# light-painting-brush.net
KiCad netlist of a schematic drawn in EAGLE
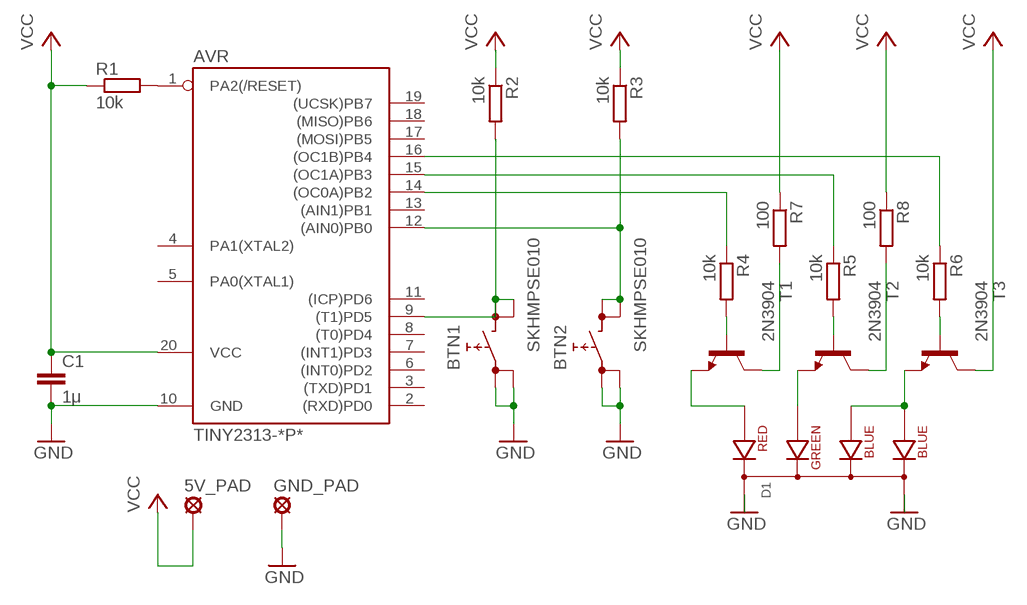
[diagram p0: schematic, sheet 1]

(export (version "E")
  (design (tool "Eeschema 10.0.6"))
  (components
    (comp (ref "5V_PAD")
      (value "LSP10")
      (footprint "eagle-import:LSP10")
      (libsource (lib "eagle-import") (part "LSP10"))
    )
    (comp (ref "AVR")
      (value "TINY2313-*P*")
      (footprint "eagle-import:DIL20")
      (libsource (lib "eagle-import") (part "TINY2313-P"))
    )
    (comp (ref "BTN1")
      (value "SKHMPSE010")
      (footprint "eagle-import:SKHMPXE010")
      (libsource (lib "eagle-import") (part "SKHMPE010S"))
    )
    (comp (ref "BTN2")
      (value "SKHMPSE010")
      (footprint "eagle-import:SKHMPXE010")
      (libsource (lib "eagle-import") (part "SKHMPE010S"))
    )
    (comp (ref "C1")
      (value "1μ")
      (footprint "eagle-import:C1206")
      (libsource (lib "eagle-import") (part "C-EUC1206"))
    )
    (comp (ref "D1")
      (value "LED-RGB-CC-THRUDIFFUSE")
      (footprint "eagle-import:LED-RGB-THRU")
      (libsource (lib "eagle-import") (part "LED-RGB-CC-THRUDIFFUSE"))
    )
    (comp (ref "GND_PAD")
      (value "LSP10")
      (footprint "eagle-import:LSP10")
      (libsource (lib "eagle-import") (part "LSP10"))
    )
    (comp (ref "R1")
      (value "10k")
      (footprint "eagle-import:R1206")
      (libsource (lib "eagle-import") (part "R-EU_R1206"))
    )
    (comp (ref "R2")
      (value "10k")
      (footprint "eagle-import:R1206")
      (libsource (lib "eagle-import") (part "R-EU_R1206"))
    )
    (comp (ref "R3")
      (value "10k")
      (footprint "eagle-import:R1206")
      (libsource (lib "eagle-import") (part "R-EU_R1206"))
    )
    (comp (ref "R4")
      (value "10k")
      (footprint "eagle-import:R1206")
      (libsource (lib "eagle-import") (part "R-EU_R1206"))
    )
    (comp (ref "R5")
      (value "10k")
      (footprint "eagle-import:R1206")
      (libsource (lib "eagle-import") (part "R-EU_R1206"))
    )
    (comp (ref "R6")
      (value "10k")
      (footprint "eagle-import:R1206")
      (libsource (lib "eagle-import") (part "R-EU_R1206"))
    )
    (comp (ref "R7")
      (value "100")
      (footprint "eagle-import:R1206")
      (libsource (lib "eagle-import") (part "R-EU_R1206"))
    )
    (comp (ref "R8")
      (value "100")
      (footprint "eagle-import:R1206")
      (libsource (lib "eagle-import") (part "R-EU_R1206"))
    )
    (comp (ref "T1")
      (value "2N3904")
      (footprint "eagle-import:TO92")
      (libsource (lib "eagle-import") (part "2N3904"))
    )
    (comp (ref "T2")
      (value "2N3904")
      (footprint "eagle-import:TO92")
      (libsource (lib "eagle-import") (part "2N3904"))
    )
    (comp (ref "T3")
      (value "2N3904")
      (footprint "eagle-import:TO92")
      (libsource (lib "eagle-import") (part "2N3904"))
    )
  )
  (nets
    (net (code "1") (name "GND") (class "Default")
      (node (ref "AVR") (pin "10") (pinfunction "GND_10") (pintype "power_in"))
      (node (ref "BTN1") (pin "1") (pinfunction "1.1_1") (pintype "passive"))
      (node (ref "BTN1") (pin "2") (pinfunction "1.2_2") (pintype "passive"))
      (node (ref "BTN2") (pin "1") (pinfunction "1.1_1") (pintype "passive"))
      (node (ref "BTN2") (pin "2") (pinfunction "1.2_2") (pintype "passive"))
      (node (ref "C1") (pin "2") (pinfunction "2_2") (pintype "passive"))
      (node (ref "D1") (pin "CATHODE1") (pinfunction "CATHODE1_CATHODE1") (pintype "bidirectional"))
      (node (ref "D1") (pin "CATHODE2") (pinfunction "CATHODE2_CATHODE2") (pintype "bidirectional"))
      (node (ref "GND_PAD") (pin "MP") (pinfunction "MP_MP") (pintype "passive"))
    )
    (net (code "2") (name "Net-(AVR-(AIN0)PB0)") (class "Default")
      (node (ref "AVR") (pin "12") (pinfunction "(AIN0)PB0_12") (pintype "bidirectional"))
      (node (ref "BTN2") (pin "3") (pinfunction "2.1_3") (pintype "passive"))
      (node (ref "BTN2") (pin "4") (pinfunction "2.2_4") (pintype "passive"))
      (node (ref "R3") (pin "2") (pinfunction "2_2") (pintype "passive"))
    )
    (net (code "3") (name "Net-(AVR-(OC0A)PB2)") (class "Default")
      (node (ref "AVR") (pin "14") (pinfunction "(OC0A)PB2_14") (pintype "bidirectional"))
      (node (ref "R4") (pin "1") (pinfunction "1_1") (pintype "passive"))
    )
    (net (code "4") (name "Net-(AVR-(OC1A)PB3)") (class "Default")
      (node (ref "AVR") (pin "15") (pinfunction "(OC1A)PB3_15") (pintype "bidirectional"))
      (node (ref "R5") (pin "1") (pinfunction "1_1") (pintype "passive"))
    )
    (net (code "5") (name "Net-(AVR-(OC1B)PB4)") (class "Default")
      (node (ref "AVR") (pin "16") (pinfunction "(OC1B)PB4_16") (pintype "bidirectional"))
      (node (ref "R6") (pin "1") (pinfunction "1_1") (pintype "passive"))
    )
    (net (code "6") (name "Net-(AVR-(T1)PD5)") (class "Default")
      (node (ref "AVR") (pin "9") (pinfunction "(T1)PD5_9") (pintype "bidirectional"))
      (node (ref "BTN1") (pin "3") (pinfunction "2.1_3") (pintype "passive"))
      (node (ref "BTN1") (pin "4") (pinfunction "2.2_4") (pintype "passive"))
      (node (ref "R2") (pin "2") (pinfunction "2_2") (pintype "passive"))
    )
    (net (code "7") (name "Net-(AVR-PA2({slash}RESET))") (class "Default")
      (node (ref "AVR") (pin "1") (pinfunction "PA2(/RESET)_1") (pintype "input"))
      (node (ref "R1") (pin "2") (pinfunction "2_2") (pintype "passive"))
    )
    (net (code "8") (name "Net-(T1-B)") (class "Default")
      (node (ref "R4") (pin "2") (pinfunction "2_2") (pintype "passive"))
      (node (ref "T1") (pin "2") (pinfunction "B_2") (pintype "passive"))
    )
    (net (code "9") (name "Net-(T1-C)") (class "Default")
      (node (ref "R7") (pin "2") (pinfunction "2_2") (pintype "passive"))
      (node (ref "T1") (pin "1") (pinfunction "C_1") (pintype "passive"))
    )
    (net (code "10") (name "Net-(T1-E)") (class "Default")
      (node (ref "D1") (pin "RED") (pinfunction "RED_RED") (pintype "bidirectional"))
      (node (ref "T1") (pin "3") (pinfunction "E_3") (pintype "passive"))
    )
    (net (code "11") (name "Net-(T2-B)") (class "Default")
      (node (ref "R5") (pin "2") (pinfunction "2_2") (pintype "passive"))
      (node (ref "T2") (pin "2") (pinfunction "B_2") (pintype "passive"))
    )
    (net (code "12") (name "Net-(T2-C)") (class "Default")
      (node (ref "R8") (pin "2") (pinfunction "2_2") (pintype "passive"))
      (node (ref "T2") (pin "1") (pinfunction "C_1") (pintype "passive"))
    )
    (net (code "13") (name "Net-(T2-E)") (class "Default")
      (node (ref "D1") (pin "GREEN") (pinfunction "GREEN_GREEN") (pintype "bidirectional"))
      (node (ref "T2") (pin "3") (pinfunction "E_3") (pintype "passive"))
    )
    (net (code "14") (name "Net-(T3-B)") (class "Default")
      (node (ref "R6") (pin "2") (pinfunction "2_2") (pintype "passive"))
      (node (ref "T3") (pin "2") (pinfunction "B_2") (pintype "passive"))
    )
    (net (code "15") (name "Net-(T3-E)") (class "Default")
      (node (ref "D1") (pin "BLUE1") (pinfunction "BLUE1_BLUE1") (pintype "bidirectional"))
      (node (ref "D1") (pin "BLUE2") (pinfunction "BLUE2_BLUE2") (pintype "bidirectional"))
      (node (ref "T3") (pin "3") (pinfunction "E_3") (pintype "passive"))
    )
    (net (code "16") (name "VCC") (class "Default")
      (node (ref "5V_PAD") (pin "MP") (pinfunction "MP_MP") (pintype "passive"))
      (node (ref "AVR") (pin "20") (pinfunction "VCC_20") (pintype "power_in"))
      (node (ref "C1") (pin "1") (pinfunction "1_1") (pintype "passive"))
      (node (ref "R1") (pin "1") (pinfunction "1_1") (pintype "passive"))
      (node (ref "R2") (pin "1") (pinfunction "1_1") (pintype "passive"))
      (node (ref "R3") (pin "1") (pinfunction "1_1") (pintype "passive"))
      (node (ref "R7") (pin "1") (pinfunction "1_1") (pintype "passive"))
      (node (ref "R8") (pin "1") (pinfunction "1_1") (pintype "passive"))
      (node (ref "T3") (pin "1") (pinfunction "C_1") (pintype "passive"))
    )
    (net (code "17") (name "unconnected-(AVR-(AIN1)PB1-Pad13)") (class "Default")
      (node (ref "AVR") (pin "13") (pinfunction "(AIN1)PB1_13") (pintype "bidirectional"))
    )
    (net (code "18") (name "unconnected-(AVR-(ICP)PD6-Pad11)") (class "Default")
      (node (ref "AVR") (pin "11") (pinfunction "(ICP)PD6_11") (pintype "bidirectional"))
    )
    (net (code "19") (name "unconnected-(AVR-(INT0)PD2-Pad6)") (class "Default")
      (node (ref "AVR") (pin "6") (pinfunction "(INT0)PD2_6") (pintype "bidirectional"))
    )
    (net (code "20") (name "unconnected-(AVR-(INT1)PD3-Pad7)") (class "Default")
      (node (ref "AVR") (pin "7") (pinfunction "(INT1)PD3_7") (pintype "bidirectional"))
    )
    (net (code "21") (name "unconnected-(AVR-(MISO)PB6-Pad18)") (class "Default")
      (node (ref "AVR") (pin "18") (pinfunction "(MISO)PB6_18") (pintype "bidirectional"))
    )
    (net (code "22") (name "unconnected-(AVR-(MOSI)PB5-Pad17)") (class "Default")
      (node (ref "AVR") (pin "17") (pinfunction "(MOSI)PB5_17") (pintype "bidirectional"))
    )
    (net (code "23") (name "unconnected-(AVR-(RXD)PD0-Pad2)") (class "Default")
      (node (ref "AVR") (pin "2") (pinfunction "(RXD)PD0_2") (pintype "bidirectional"))
    )
    (net (code "24") (name "unconnected-(AVR-(T0)PD4-Pad8)") (class "Default")
      (node (ref "AVR") (pin "8") (pinfunction "(T0)PD4_8") (pintype "bidirectional"))
    )
    (net (code "25") (name "unconnected-(AVR-(TXD)PD1-Pad3)") (class "Default")
      (node (ref "AVR") (pin "3") (pinfunction "(TXD)PD1_3") (pintype "bidirectional"))
    )
    (net (code "26") (name "unconnected-(AVR-(UCSK)PB7-Pad19)") (class "Default")
      (node (ref "AVR") (pin "19") (pinfunction "(UCSK)PB7_19") (pintype "bidirectional"))
    )
    (net (code "27") (name "unconnected-(AVR-PA0(XTAL1)-Pad5)") (class "Default")
      (node (ref "AVR") (pin "5") (pinfunction "PA0(XTAL1)_5") (pintype "bidirectional"))
    )
    (net (code "28") (name "unconnected-(AVR-PA1(XTAL2)-Pad4)") (class "Default")
      (node (ref "AVR") (pin "4") (pinfunction "PA1(XTAL2)_4") (pintype "bidirectional"))
    )
  )
)
